# Solar_Scramble.net
KiCad netlist of a schematic drawn in EAGLE
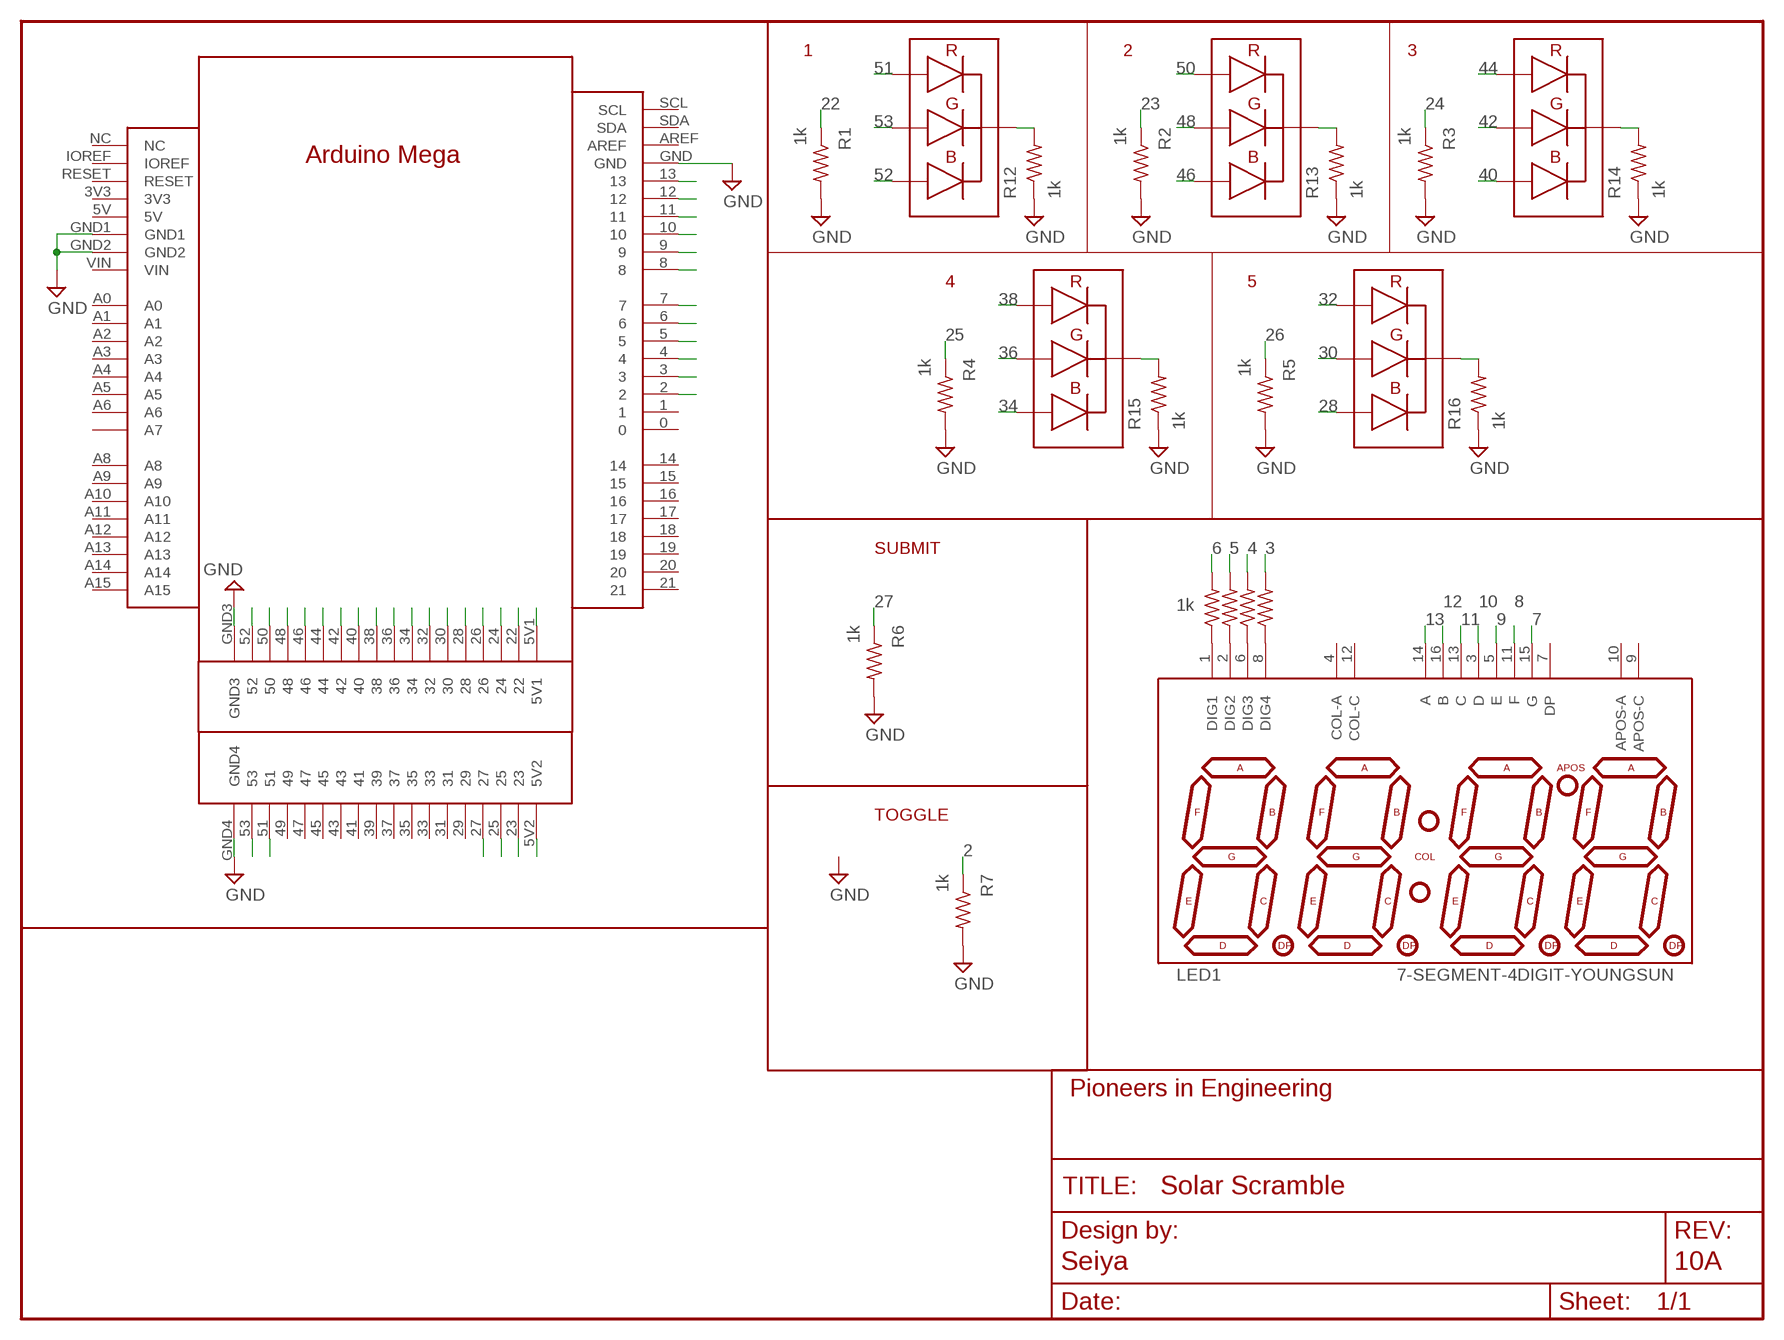
[diagram p0: schematic, sheet 1]

(export (version "E")
  (design (tool "Eeschema 10.0.6"))
  (components
    (comp (ref "LED1")
      (value "7-SEGMENT-4DIGIT-YOUNGSUN")
      (footprint "eagle-import:7-SEGMENT-4DIGIT-YOUNGSUN")
      (libsource (lib "eagle-import") (part "7-SEGMENT-4DIGIT-YOUNGSUN"))
    )
    (comp (ref "R1")
      (value "1k")
      (footprint "eagle-import:R0603")
      (fields (field (name "MANUFACTURER") "Rohm Semiconductor"))
      (libsource (lib "eagle-import") (part "R-US_R0603"))
    )
    (comp (ref "R2")
      (value "1k")
      (footprint "eagle-import:R0603")
      (fields (field (name "MANUFACTURER") "Rohm Semiconductor"))
      (libsource (lib "eagle-import") (part "R-US_R0603"))
    )
    (comp (ref "R3")
      (value "1k")
      (footprint "eagle-import:R0603")
      (fields (field (name "MANUFACTURER") "Rohm Semiconductor"))
      (libsource (lib "eagle-import") (part "R-US_R0603"))
    )
    (comp (ref "R4")
      (value "1k")
      (footprint "eagle-import:R0603")
      (fields (field (name "MANUFACTURER") "Rohm Semiconductor") (field (name "SPICEPREFIX") "R"))
      (libsource (lib "eagle-import") (part "R-US_R0603"))
    )
    (comp (ref "R5")
      (value "1k")
      (footprint "eagle-import:R0603")
      (fields (field (name "MANUFACTURER") "Rohm Semiconductor"))
      (libsource (lib "eagle-import") (part "R-US_R0603"))
    )
    (comp (ref "R6")
      (value "1k")
      (footprint "eagle-import:R0603")
      (fields (field (name "MANUFACTURER") "Rohm Semiconductor"))
      (libsource (lib "eagle-import") (part "R-US_R0603"))
    )
    (comp (ref "R7")
      (value "1k")
      (footprint "eagle-import:R0603")
      (fields (field (name "MANUFACTURER") "Rohm Semiconductor"))
      (libsource (lib "eagle-import") (part "R-US_R0603"))
    )
    (comp (ref "R8")
      (value "1ik")
      (footprint "eagle-import:R0603")
      (fields (field (name "MANUFACTURER") "Rohm Semiconductor"))
      (libsource (lib "eagle-import") (part "R-US_R0603"))
    )
    (comp (ref "R9")
      (value "1k")
      (footprint "eagle-import:R0603")
      (fields (field (name "MANUFACTURER") "Rohm Semiconductor"))
      (libsource (lib "eagle-import") (part "R-US_R0603"))
    )
    (comp (ref "R10")
      (value "1k")
      (footprint "eagle-import:R0603")
      (fields (field (name "MANUFACTURER") "Rohm Semiconductor"))
      (libsource (lib "eagle-import") (part "R-US_R0603"))
    )
    (comp (ref "R11")
      (value "1k")
      (footprint "eagle-import:R0603")
      (fields (field (name "MANUFACTURER") "Rohm Semiconductor"))
      (libsource (lib "eagle-import") (part "R-US_R0603"))
    )
    (comp (ref "R12")
      (value "1k")
      (footprint "eagle-import:R0603")
      (fields (field (name "MANUFACTURER") "Rohm Semiconductor"))
      (libsource (lib "eagle-import") (part "R-US_R0603"))
    )
    (comp (ref "R13")
      (value "1k")
      (footprint "eagle-import:R0603")
      (fields (field (name "MANUFACTURER") "Rohm Semiconductor"))
      (libsource (lib "eagle-import") (part "R-US_R0603"))
    )
    (comp (ref "R14")
      (value "1k")
      (footprint "eagle-import:R0603")
      (fields (field (name "MANUFACTURER") "Rohm Semiconductor"))
      (libsource (lib "eagle-import") (part "R-US_R0603"))
    )
    (comp (ref "R15")
      (value "1k")
      (footprint "eagle-import:R0603")
      (fields (field (name "MANUFACTURER") "Rohm Semiconductor"))
      (libsource (lib "eagle-import") (part "R-US_R0603"))
    )
    (comp (ref "R16")
      (value "1k")
      (footprint "eagle-import:R0603")
      (fields (field (name "MANUFACTURER") "Rohm Semiconductor"))
      (libsource (lib "eagle-import") (part "R-US_R0603"))
    )
    (comp (ref "U$1")
      (value "ARD_MEGA")
      (footprint "eagle-import:ARD_MEGA")
      (libsource (lib "eagle-import") (part "ARD_MEGA"))
    )
    (comp (ref "U$2")
      (value "TRI-LED")
      (footprint "eagle-import:TRI-LED")
      (libsource (lib "eagle-import") (part "TRI-LED"))
    )
    (comp (ref "U$3")
      (value "TRI-LED")
      (footprint "eagle-import:TRI-LED")
      (libsource (lib "eagle-import") (part "TRI-LED"))
    )
    (comp (ref "U$4")
      (value "TRI-LED")
      (footprint "eagle-import:TRI-LED")
      (libsource (lib "eagle-import") (part "TRI-LED"))
    )
    (comp (ref "U$5")
      (value "TRI-LED")
      (footprint "eagle-import:TRI-LED")
      (libsource (lib "eagle-import") (part "TRI-LED"))
    )
    (comp (ref "U$6")
      (value "TRI-LED")
      (footprint "eagle-import:TRI-LED")
      (libsource (lib "eagle-import") (part "TRI-LED"))
    )
  )
  (nets
    (net (code "1") (name "/2") (class "Default")
      (node (ref "R7") (pin "1") (pinfunction "1_1") (pintype "passive"))
      (node (ref "U$1") (pin "2") (pinfunction "2_2") (pintype "bidirectional"))
    )
    (net (code "2") (name "/3") (class "Default")
      (node (ref "R11") (pin "2") (pinfunction "2_2") (pintype "passive"))
      (node (ref "U$1") (pin "3") (pinfunction "3_3") (pintype "bidirectional"))
    )
    (net (code "3") (name "/4") (class "Default")
      (node (ref "R10") (pin "2") (pinfunction "2_2") (pintype "passive"))
      (node (ref "U$1") (pin "4") (pinfunction "4_4") (pintype "bidirectional"))
    )
    (net (code "4") (name "/5") (class "Default")
      (node (ref "R9") (pin "2") (pinfunction "2_2") (pintype "passive"))
      (node (ref "U$1") (pin "5") (pinfunction "5_5") (pintype "bidirectional"))
    )
    (net (code "5") (name "/5V") (class "Default")
      (node (ref "U$1") (pin "5V1") (pinfunction "5V1_5V1") (pintype "bidirectional"))
      (node (ref "U$1") (pin "5V2") (pinfunction "5V2_5V2") (pintype "bidirectional"))
    )
    (net (code "6") (name "/6") (class "Default")
      (node (ref "R8") (pin "2") (pinfunction "2_2") (pintype "passive"))
      (node (ref "U$1") (pin "6") (pinfunction "6_6") (pintype "bidirectional"))
    )
    (net (code "7") (name "/7") (class "Default")
      (node (ref "LED1") (pin "15") (pinfunction "G_15") (pintype "bidirectional"))
      (node (ref "U$1") (pin "7") (pinfunction "7_7") (pintype "bidirectional"))
    )
    (net (code "8") (name "/8") (class "Default")
      (node (ref "LED1") (pin "11") (pinfunction "F_11") (pintype "bidirectional"))
      (node (ref "U$1") (pin "8") (pinfunction "8_8") (pintype "bidirectional"))
    )
    (net (code "9") (name "/9") (class "Default")
      (node (ref "LED1") (pin "5") (pinfunction "E_5") (pintype "bidirectional"))
      (node (ref "U$1") (pin "9") (pinfunction "9_9") (pintype "bidirectional"))
    )
    (net (code "10") (name "/10") (class "Default")
      (node (ref "LED1") (pin "3") (pinfunction "D_3") (pintype "bidirectional"))
      (node (ref "U$1") (pin "10") (pinfunction "10_10") (pintype "bidirectional"))
    )
    (net (code "11") (name "/11") (class "Default")
      (node (ref "LED1") (pin "13") (pinfunction "C_13") (pintype "bidirectional"))
      (node (ref "U$1") (pin "11") (pinfunction "11_11") (pintype "bidirectional"))
    )
    (net (code "12") (name "/12") (class "Default")
      (node (ref "LED1") (pin "16") (pinfunction "B_16") (pintype "bidirectional"))
      (node (ref "U$1") (pin "12") (pinfunction "12_12") (pintype "bidirectional"))
    )
    (net (code "13") (name "/13") (class "Default")
      (node (ref "LED1") (pin "14") (pinfunction "A_14") (pintype "bidirectional"))
      (node (ref "U$1") (pin "13") (pinfunction "13_13") (pintype "bidirectional"))
    )
    (net (code "14") (name "/22") (class "Default")
      (node (ref "R1") (pin "1") (pinfunction "1_1") (pintype "passive"))
      (node (ref "U$1") (pin "22") (pinfunction "22_22") (pintype "bidirectional"))
    )
    (net (code "15") (name "/23") (class "Default")
      (node (ref "R2") (pin "1") (pinfunction "1_1") (pintype "passive"))
      (node (ref "U$1") (pin "23") (pinfunction "23_23") (pintype "bidirectional"))
    )
    (net (code "16") (name "/24") (class "Default")
      (node (ref "R3") (pin "1") (pinfunction "1_1") (pintype "passive"))
      (node (ref "U$1") (pin "24") (pinfunction "24_24") (pintype "bidirectional"))
    )
    (net (code "17") (name "/25") (class "Default")
      (node (ref "R4") (pin "1") (pinfunction "1_1") (pintype "passive"))
      (node (ref "U$1") (pin "25") (pinfunction "25_25") (pintype "bidirectional"))
    )
    (net (code "18") (name "/26") (class "Default")
      (node (ref "R5") (pin "1") (pinfunction "1_1") (pintype "passive"))
      (node (ref "U$1") (pin "26") (pinfunction "26_26") (pintype "bidirectional"))
    )
    (net (code "19") (name "/27") (class "Default")
      (node (ref "R6") (pin "1") (pinfunction "1_1") (pintype "passive"))
      (node (ref "U$1") (pin "27") (pinfunction "27_27") (pintype "bidirectional"))
    )
    (net (code "20") (name "/28") (class "Default")
      (node (ref "U$1") (pin "28") (pinfunction "28_28") (pintype "bidirectional"))
      (node (ref "U$5") (pin "B") (pinfunction "B_B") (pintype "bidirectional"))
    )
    (net (code "21") (name "/30") (class "Default")
      (node (ref "U$1") (pin "30") (pinfunction "30_30") (pintype "bidirectional"))
      (node (ref "U$5") (pin "G") (pinfunction "G_G") (pintype "bidirectional"))
    )
    (net (code "22") (name "/32") (class "Default")
      (node (ref "U$1") (pin "32") (pinfunction "32_32") (pintype "bidirectional"))
      (node (ref "U$5") (pin "R") (pinfunction "R_R") (pintype "bidirectional"))
    )
    (net (code "23") (name "/34") (class "Default")
      (node (ref "U$1") (pin "34") (pinfunction "34_34") (pintype "bidirectional"))
      (node (ref "U$4") (pin "B") (pinfunction "B_B") (pintype "bidirectional"))
    )
    (net (code "24") (name "/36") (class "Default")
      (node (ref "U$1") (pin "36") (pinfunction "36_36") (pintype "bidirectional"))
      (node (ref "U$4") (pin "G") (pinfunction "G_G") (pintype "bidirectional"))
    )
    (net (code "25") (name "/38") (class "Default")
      (node (ref "U$1") (pin "38") (pinfunction "38_38") (pintype "bidirectional"))
      (node (ref "U$4") (pin "R") (pinfunction "R_R") (pintype "bidirectional"))
    )
    (net (code "26") (name "/40") (class "Default")
      (node (ref "U$1") (pin "40") (pinfunction "40_40") (pintype "bidirectional"))
      (node (ref "U$3") (pin "B") (pinfunction "B_B") (pintype "bidirectional"))
    )
    (net (code "27") (name "/42") (class "Default")
      (node (ref "U$1") (pin "42") (pinfunction "42_42") (pintype "bidirectional"))
      (node (ref "U$3") (pin "G") (pinfunction "G_G") (pintype "bidirectional"))
    )
    (net (code "28") (name "/44") (class "Default")
      (node (ref "U$1") (pin "44") (pinfunction "44_44") (pintype "bidirectional"))
      (node (ref "U$3") (pin "R") (pinfunction "R_R") (pintype "bidirectional"))
    )
    (net (code "29") (name "/46") (class "Default")
      (node (ref "U$1") (pin "46") (pinfunction "46_46") (pintype "bidirectional"))
      (node (ref "U$6") (pin "B") (pinfunction "B_B") (pintype "bidirectional"))
    )
    (net (code "30") (name "/48") (class "Default")
      (node (ref "U$1") (pin "48") (pinfunction "48_48") (pintype "bidirectional"))
      (node (ref "U$6") (pin "G") (pinfunction "G_G") (pintype "bidirectional"))
    )
    (net (code "31") (name "/50") (class "Default")
      (node (ref "U$1") (pin "50") (pinfunction "50_50") (pintype "bidirectional"))
      (node (ref "U$6") (pin "R") (pinfunction "R_R") (pintype "bidirectional"))
    )
    (net (code "32") (name "/51") (class "Default")
      (node (ref "U$1") (pin "51") (pinfunction "51_51") (pintype "bidirectional"))
      (node (ref "U$2") (pin "R") (pinfunction "R_R") (pintype "bidirectional"))
    )
    (net (code "33") (name "/52") (class "Default")
      (node (ref "U$1") (pin "52") (pinfunction "52_52") (pintype "bidirectional"))
      (node (ref "U$2") (pin "B") (pinfunction "B_B") (pintype "bidirectional"))
    )
    (net (code "34") (name "/53") (class "Default")
      (node (ref "U$1") (pin "53") (pinfunction "53_53") (pintype "bidirectional"))
      (node (ref "U$2") (pin "G") (pinfunction "G_G") (pintype "bidirectional"))
    )
    (net (code "35") (name "GND") (class "Default")
      (node (ref "R1") (pin "2") (pinfunction "2_2") (pintype "passive"))
      (node (ref "R12") (pin "1") (pinfunction "1_1") (pintype "passive"))
      (node (ref "R13") (pin "1") (pinfunction "1_1") (pintype "passive"))
      (node (ref "R14") (pin "1") (pinfunction "1_1") (pintype "passive"))
      (node (ref "R15") (pin "1") (pinfunction "1_1") (pintype "passive"))
      (node (ref "R16") (pin "1") (pinfunction "1_1") (pintype "passive"))
      (node (ref "R2") (pin "2") (pinfunction "2_2") (pintype "passive"))
      (node (ref "R3") (pin "2") (pinfunction "2_2") (pintype "passive"))
      (node (ref "R4") (pin "2") (pinfunction "2_2") (pintype "passive"))
      (node (ref "R5") (pin "2") (pinfunction "2_2") (pintype "passive"))
      (node (ref "R6") (pin "2") (pinfunction "2_2") (pintype "passive"))
      (node (ref "R7") (pin "2") (pinfunction "2_2") (pintype "passive"))
      (node (ref "U$1") (pin "GND") (pinfunction "GND_GND") (pintype "bidirectional"))
      (node (ref "U$1") (pin "GND1") (pinfunction "GND1_GND1") (pintype "bidirectional"))
      (node (ref "U$1") (pin "GND2") (pinfunction "GND2_GND2") (pintype "bidirectional"))
      (node (ref "U$1") (pin "GND3") (pinfunction "GND3_GND3") (pintype "bidirectional"))
      (node (ref "U$1") (pin "GND4") (pinfunction "GND4_GND4") (pintype "bidirectional"))
    )
    (net (code "36") (name "Net-(LED1-DIG1)") (class "Default")
      (node (ref "LED1") (pin "1") (pinfunction "DIG1_1") (pintype "bidirectional"))
      (node (ref "R8") (pin "1") (pinfunction "1_1") (pintype "passive"))
    )
    (net (code "37") (name "Net-(LED1-DIG2)") (class "Default")
      (node (ref "LED1") (pin "2") (pinfunction "DIG2_2") (pintype "bidirectional"))
      (node (ref "R9") (pin "1") (pinfunction "1_1") (pintype "passive"))
    )
    (net (code "38") (name "Net-(LED1-DIG3)") (class "Default")
      (node (ref "LED1") (pin "6") (pinfunction "DIG3_6") (pintype "bidirectional"))
      (node (ref "R10") (pin "1") (pinfunction "1_1") (pintype "passive"))
    )
    (net (code "39") (name "Net-(LED1-DIG4)") (class "Default")
      (node (ref "LED1") (pin "8") (pinfunction "DIG4_8") (pintype "bidirectional"))
      (node (ref "R11") (pin "1") (pinfunction "1_1") (pintype "passive"))
    )
    (net (code "40") (name "Net-(U$2-CAT)") (class "Default")
      (node (ref "R12") (pin "2") (pinfunction "2_2") (pintype "passive"))
      (node (ref "U$2") (pin "GND") (pinfunction "CAT_GND") (pintype "bidirectional"))
    )
    (net (code "41") (name "Net-(U$3-CAT)") (class "Default")
      (node (ref "R14") (pin "2") (pinfunction "2_2") (pintype "passive"))
      (node (ref "U$3") (pin "GND") (pinfunction "CAT_GND") (pintype "bidirectional"))
    )
    (net (code "42") (name "Net-(U$4-CAT)") (class "Default")
      (node (ref "R15") (pin "2") (pinfunction "2_2") (pintype "passive"))
      (node (ref "U$4") (pin "GND") (pinfunction "CAT_GND") (pintype "bidirectional"))
    )
    (net (code "43") (name "Net-(U$5-CAT)") (class "Default")
      (node (ref "R16") (pin "2") (pinfunction "2_2") (pintype "passive"))
      (node (ref "U$5") (pin "GND") (pinfunction "CAT_GND") (pintype "bidirectional"))
    )
    (net (code "44") (name "Net-(U$6-CAT)") (class "Default")
      (node (ref "R13") (pin "2") (pinfunction "2_2") (pintype "passive"))
      (node (ref "U$6") (pin "GND") (pinfunction "CAT_GND") (pintype "bidirectional"))
    )
    (net (code "45") (name "unconnected-(LED1-APOS-A-Pad10)") (class "Default")
      (node (ref "LED1") (pin "10") (pinfunction "APOS-A_10") (pintype "bidirectional"))
    )
    (net (code "46") (name "unconnected-(LED1-APOS-C-Pad9)") (class "Default")
      (node (ref "LED1") (pin "9") (pinfunction "APOS-C_9") (pintype "bidirectional"))
    )
    (net (code "47") (name "unconnected-(LED1-COL-A-Pad4)") (class "Default")
      (node (ref "LED1") (pin "4") (pinfunction "COL-A_4") (pintype "bidirectional"))
    )
    (net (code "48") (name "unconnected-(LED1-COL-C-Pad12)") (class "Default")
      (node (ref "LED1") (pin "12") (pinfunction "COL-C_12") (pintype "bidirectional"))
    )
    (net (code "49") (name "unconnected-(LED1-DP-Pad7)") (class "Default")
      (node (ref "LED1") (pin "7") (pinfunction "DP_7") (pintype "bidirectional"))
    )
    (net (code "50") (name "unconnected-(U$1-Pad0)") (class "Default")
      (node (ref "U$1") (pin "0") (pinfunction "0_0") (pintype "bidirectional"))
    )
    (net (code "51") (name "unconnected-(U$1-Pad1)") (class "Default")
      (node (ref "U$1") (pin "1") (pinfunction "1_1") (pintype "bidirectional"))
    )
    (net (code "52") (name "unconnected-(U$1-Pad3V3)") (class "Default")
      (node (ref "U$1") (pin "3V3") (pinfunction "3V3_3V3") (pintype "bidirectional"))
    )
    (net (code "53") (name "unconnected-(U$1-Pad5V)") (class "Default")
      (node (ref "U$1") (pin "5V") (pinfunction "5V_5V") (pintype "bidirectional"))
    )
    (net (code "54") (name "unconnected-(U$1-Pad14)") (class "Default")
      (node (ref "U$1") (pin "14") (pinfunction "14_14") (pintype "bidirectional"))
    )
    (net (code "55") (name "unconnected-(U$1-Pad15)") (class "Default")
      (node (ref "U$1") (pin "15") (pinfunction "15_15") (pintype "bidirectional"))
    )
    (net (code "56") (name "unconnected-(U$1-Pad16)") (class "Default")
      (node (ref "U$1") (pin "16") (pinfunction "16_16") (pintype "bidirectional"))
    )
    (net (code "57") (name "unconnected-(U$1-Pad17)") (class "Default")
      (node (ref "U$1") (pin "17") (pinfunction "17_17") (pintype "bidirectional"))
    )
    (net (code "58") (name "unconnected-(U$1-Pad18)") (class "Default")
      (node (ref "U$1") (pin "18") (pinfunction "18_18") (pintype "bidirectional"))
    )
    (net (code "59") (name "unconnected-(U$1-Pad19)") (class "Default")
      (node (ref "U$1") (pin "19") (pinfunction "19_19") (pintype "bidirectional"))
    )
    (net (code "60") (name "unconnected-(U$1-Pad20)") (class "Default")
      (node (ref "U$1") (pin "20") (pinfunction "20_20") (pintype "bidirectional"))
    )
    (net (code "61") (name "unconnected-(U$1-Pad21)") (class "Default")
      (node (ref "U$1") (pin "21") (pinfunction "21_21") (pintype "bidirectional"))
    )
    (net (code "62") (name "unconnected-(U$1-Pad29)") (class "Default")
      (node (ref "U$1") (pin "29") (pinfunction "29_29") (pintype "bidirectional"))
    )
    (net (code "63") (name "unconnected-(U$1-Pad31)") (class "Default")
      (node (ref "U$1") (pin "31") (pinfunction "31_31") (pintype "bidirectional"))
    )
    (net (code "64") (name "unconnected-(U$1-Pad33)") (class "Default")
      (node (ref "U$1") (pin "33") (pinfunction "33_33") (pintype "bidirectional"))
    )
    (net (code "65") (name "unconnected-(U$1-Pad35)") (class "Default")
      (node (ref "U$1") (pin "35") (pinfunction "35_35") (pintype "bidirectional"))
    )
    (net (code "66") (name "unconnected-(U$1-Pad37)") (class "Default")
      (node (ref "U$1") (pin "37") (pinfunction "37_37") (pintype "bidirectional"))
    )
    (net (code "67") (name "unconnected-(U$1-Pad39)") (class "Default")
      (node (ref "U$1") (pin "39") (pinfunction "39_39") (pintype "bidirectional"))
    )
    (net (code "68") (name "unconnected-(U$1-Pad41)") (class "Default")
      (node (ref "U$1") (pin "41") (pinfunction "41_41") (pintype "bidirectional"))
    )
    (net (code "69") (name "unconnected-(U$1-Pad43)") (class "Default")
      (node (ref "U$1") (pin "43") (pinfunction "43_43") (pintype "bidirectional"))
    )
    (net (code "70") (name "unconnected-(U$1-Pad45)") (class "Default")
      (node (ref "U$1") (pin "45") (pinfunction "45_45") (pintype "bidirectional"))
    )
    (net (code "71") (name "unconnected-(U$1-Pad47)") (class "Default")
      (node (ref "U$1") (pin "47") (pinfunction "47_47") (pintype "bidirectional"))
    )
    (net (code "72") (name "unconnected-(U$1-Pad49)") (class "Default")
      (node (ref "U$1") (pin "49") (pinfunction "49_49") (pintype "bidirectional"))
    )
    (net (code "73") (name "unconnected-(U$1-PadA0)") (class "Default")
      (node (ref "U$1") (pin "A0") (pinfunction "A0_A0") (pintype "bidirectional"))
    )
    (net (code "74") (name "unconnected-(U$1-PadA1)") (class "Default")
      (node (ref "U$1") (pin "A1") (pinfunction "A1_A1") (pintype "bidirectional"))
    )
    (net (code "75") (name "unconnected-(U$1-PadA2)") (class "Default")
      (node (ref "U$1") (pin "A2") (pinfunction "A2_A2") (pintype "bidirectional"))
    )
    (net (code "76") (name "unconnected-(U$1-PadA3)") (class "Default")
      (node (ref "U$1") (pin "A3") (pinfunction "A3_A3") (pintype "bidirectional"))
    )
    (net (code "77") (name "unconnected-(U$1-PadA4)") (class "Default")
      (node (ref "U$1") (pin "A4") (pinfunction "A4_A4") (pintype "bidirectional"))
    )
    (net (code "78") (name "unconnected-(U$1-PadA5)") (class "Default")
      (node (ref "U$1") (pin "A5") (pinfunction "A5_A5") (pintype "bidirectional"))
    )
    (net (code "79") (name "unconnected-(U$1-PadA6)") (class "Default")
      (node (ref "U$1") (pin "A6") (pinfunction "A6_A6") (pintype "bidirectional"))
    )
    (net (code "80") (name "unconnected-(U$1-PadA7)") (class "Default")
      (node (ref "U$1") (pin "A7") (pinfunction "A7_A7") (pintype "bidirectional"))
    )
    (net (code "81") (name "unconnected-(U$1-PadA8)") (class "Default")
      (node (ref "U$1") (pin "A8") (pinfunction "A8_A8") (pintype "bidirectional"))
    )
    (net (code "82") (name "unconnected-(U$1-PadA9)") (class "Default")
      (node (ref "U$1") (pin "A9") (pinfunction "A9_A9") (pintype "bidirectional"))
    )
    (net (code "83") (name "unconnected-(U$1-PadA10)") (class "Default")
      (node (ref "U$1") (pin "A10") (pinfunction "A10_A10") (pintype "bidirectional"))
    )
    (net (code "84") (name "unconnected-(U$1-PadA11)") (class "Default")
      (node (ref "U$1") (pin "A11") (pinfunction "A11_A11") (pintype "bidirectional"))
    )
    (net (code "85") (name "unconnected-(U$1-PadA12)") (class "Default")
      (node (ref "U$1") (pin "A12") (pinfunction "A12_A12") (pintype "bidirectional"))
    )
    (net (code "86") (name "unconnected-(U$1-PadA13)") (class "Default")
      (node (ref "U$1") (pin "A13") (pinfunction "A13_A13") (pintype "bidirectional"))
    )
    (net (code "87") (name "unconnected-(U$1-PadA14)") (class "Default")
      (node (ref "U$1") (pin "A14") (pinfunction "A14_A14") (pintype "bidirectional"))
    )
    (net (code "88") (name "unconnected-(U$1-PadA15)") (class "Default")
      (node (ref "U$1") (pin "A15") (pinfunction "A15_A15") (pintype "bidirectional"))
    )
    (net (code "89") (name "unconnected-(U$1-PadAREF)") (class "Default")
      (node (ref "U$1") (pin "AREF") (pinfunction "AREF_AREF") (pintype "bidirectional"))
    )
    (net (code "90") (name "unconnected-(U$1-PadIOREF)") (class "Default")
      (node (ref "U$1") (pin "IOREF") (pinfunction "IOREF_IOREF") (pintype "bidirectional"))
    )
    (net (code "91") (name "unconnected-(U$1-PadNC)") (class "Default")
      (node (ref "U$1") (pin "NC") (pinfunction "NC_NC") (pintype "bidirectional"))
    )
    (net (code "92") (name "unconnected-(U$1-PadRESET)") (class "Default")
      (node (ref "U$1") (pin "RESET") (pinfunction "RESET_RESET") (pintype "bidirectional"))
    )
    (net (code "93") (name "unconnected-(U$1-PadSCL)") (class "Default")
      (node (ref "U$1") (pin "SCL") (pinfunction "SCL_SCL") (pintype "bidirectional"))
    )
    (net (code "94") (name "unconnected-(U$1-PadSDA)") (class "Default")
      (node (ref "U$1") (pin "SDA") (pinfunction "SDA_SDA") (pintype "bidirectional"))
    )
    (net (code "95") (name "unconnected-(U$1-PadVIN)") (class "Default")
      (node (ref "U$1") (pin "VIN") (pinfunction "VIN_VIN") (pintype "bidirectional"))
    )
  )
)
